# hector_monstertruck_shield.net
KiCad netlist of a schematic drawn in EAGLE
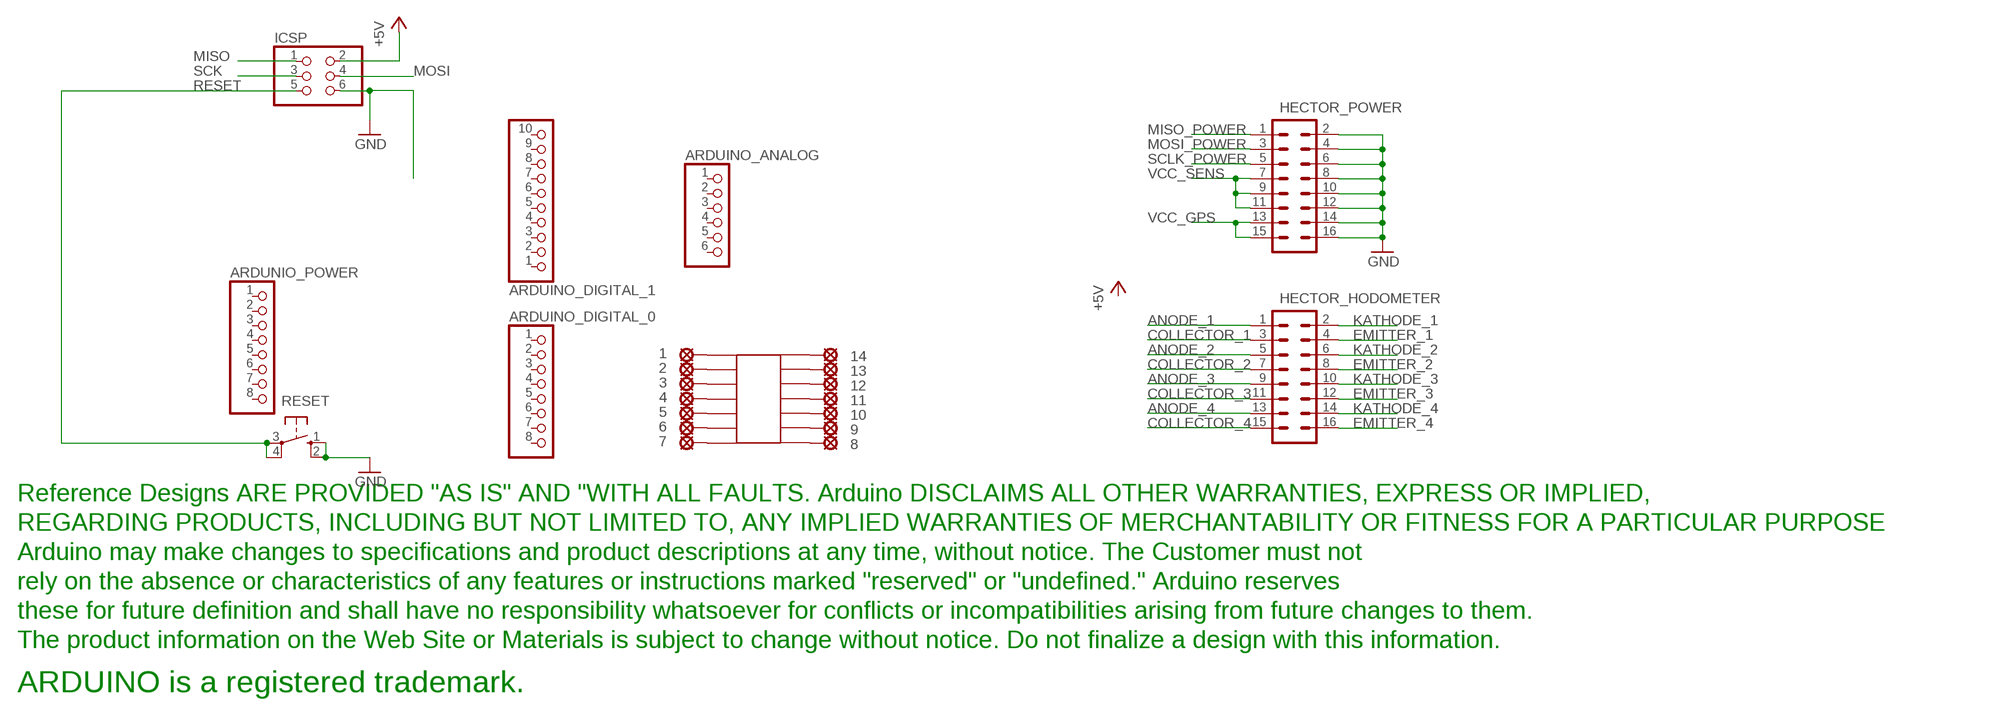
[diagram p0: schematic, sheet 1]
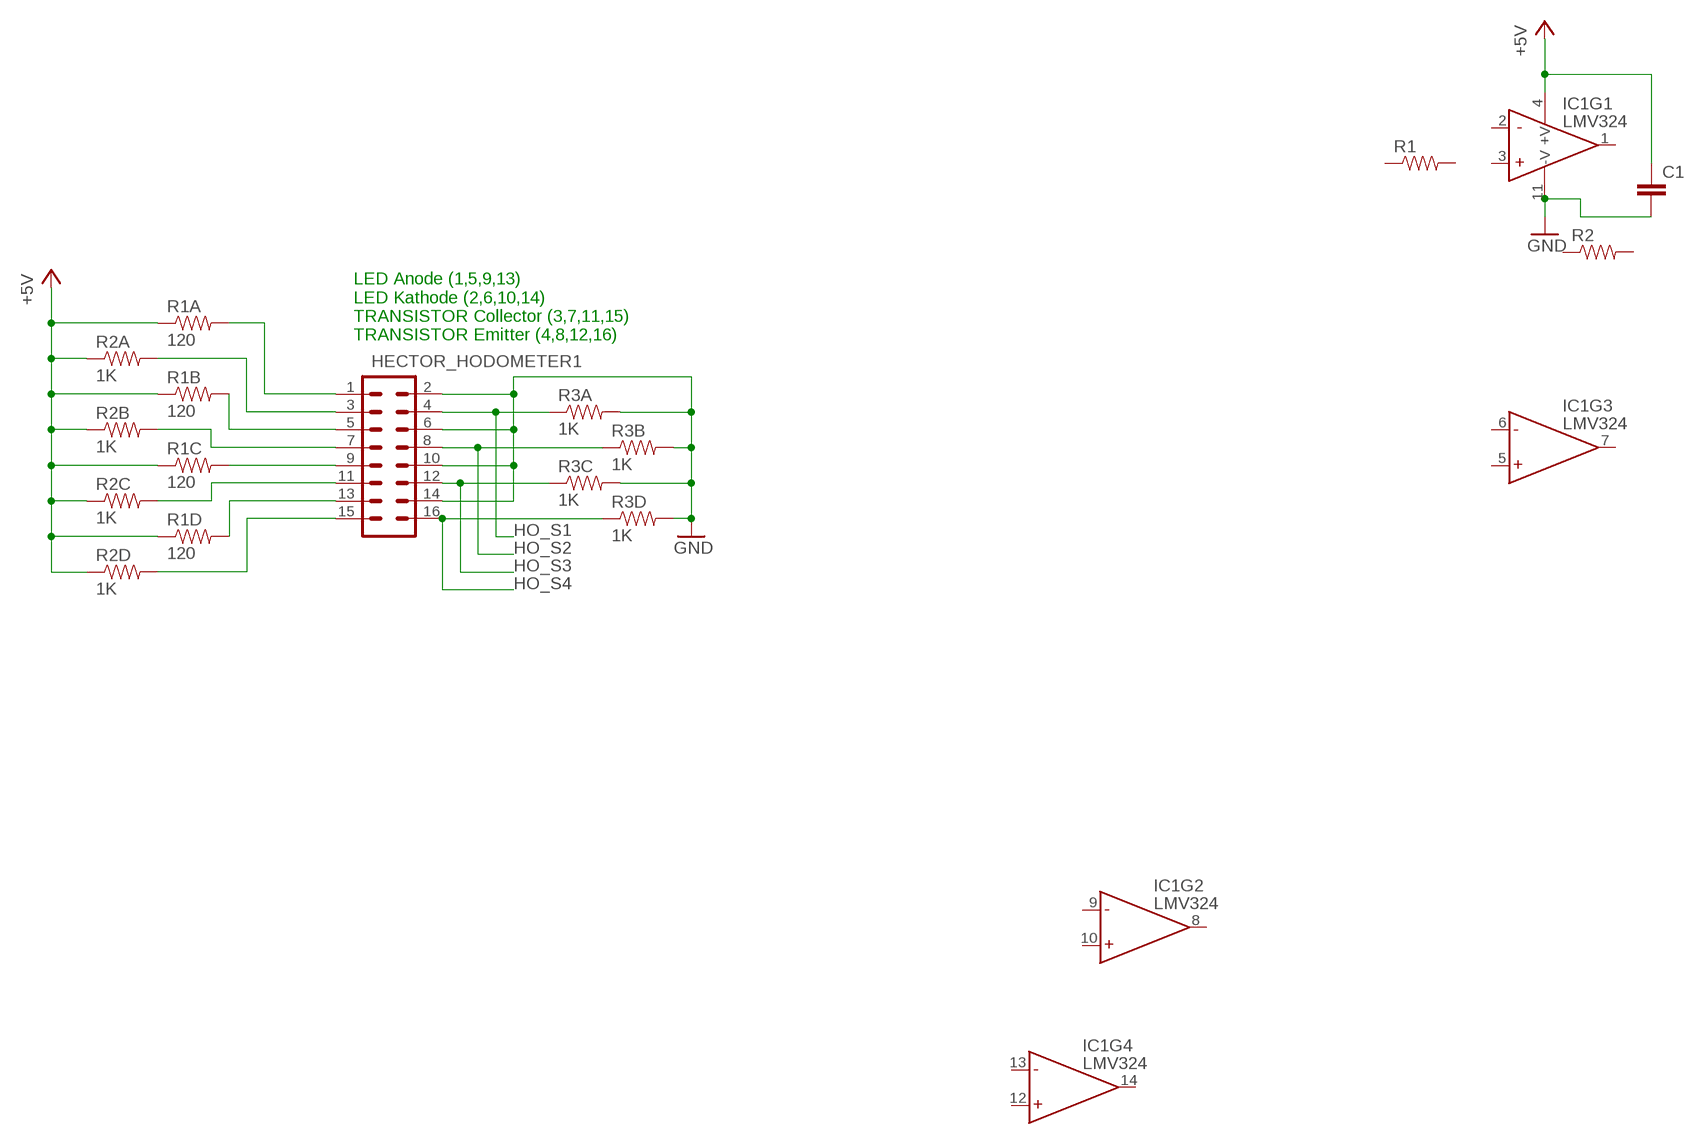
[diagram p1: schematic, sheet 2]

(export (version "E")
  (design (tool "Eeschema 10.0.6"))
  (components
    (comp (ref "C1")
      (value "CAPPTH")
      (footprint "eagle-import:CAP-PTH-SMALL")
      (libsource (lib "eagle-import") (part "CAPPTH"))
    )
    (comp (ref "HECTOR_HODOMETER1")
      (value "M08X2")
      (footprint "eagle-import:2X8")
      (libsource (lib "eagle-import") (part "M08X2"))
    )
    (comp (ref "IC1")
      (value "LMV324")
      (footprint "eagle-import:SO014")
      (libsource (lib "eagle-import") (part "LMV324"))
    )
    (comp (ref "R1")
      (value "RESISTORPTH-1/4W")
      (footprint "eagle-import:AXIAL-0.4")
      (libsource (lib "eagle-import") (part "RESISTORPTH-1/4W"))
    )
    (comp (ref "R1A")
      (value "120")
      (footprint "eagle-import:AXIAL-0.4")
      (libsource (lib "eagle-import") (part "RESISTORPTH-1/4W"))
    )
    (comp (ref "R1B")
      (value "120")
      (footprint "eagle-import:AXIAL-0.4")
      (libsource (lib "eagle-import") (part "RESISTORPTH-1/4W"))
    )
    (comp (ref "R1C")
      (value "120")
      (footprint "eagle-import:AXIAL-0.4")
      (libsource (lib "eagle-import") (part "RESISTORPTH-1/4W"))
    )
    (comp (ref "R1D")
      (value "120")
      (footprint "eagle-import:AXIAL-0.4")
      (libsource (lib "eagle-import") (part "RESISTORPTH-1/4W"))
    )
    (comp (ref "R2")
      (value "RESISTORPTH-1/4W")
      (footprint "eagle-import:AXIAL-0.4")
      (libsource (lib "eagle-import") (part "RESISTORPTH-1/4W"))
    )
    (comp (ref "R2A")
      (value "1K")
      (footprint "eagle-import:AXIAL-0.4")
      (libsource (lib "eagle-import") (part "RESISTORPTH-1/4W"))
    )
    (comp (ref "R2B")
      (value "1K")
      (footprint "eagle-import:AXIAL-0.4")
      (libsource (lib "eagle-import") (part "RESISTORPTH-1/4W"))
    )
    (comp (ref "R2C")
      (value "1K")
      (footprint "eagle-import:AXIAL-0.4")
      (libsource (lib "eagle-import") (part "RESISTORPTH-1/4W"))
    )
    (comp (ref "R2D")
      (value "1K")
      (footprint "eagle-import:AXIAL-0.4")
      (libsource (lib "eagle-import") (part "RESISTORPTH-1/4W"))
    )
    (comp (ref "R3A")
      (value "1K")
      (footprint "eagle-import:AXIAL-0.4")
      (libsource (lib "eagle-import") (part "RESISTORPTH-1/4W"))
    )
    (comp (ref "R3B")
      (value "1K")
      (footprint "eagle-import:AXIAL-0.4")
      (libsource (lib "eagle-import") (part "RESISTORPTH-1/4W"))
    )
    (comp (ref "R3C")
      (value "1K")
      (footprint "eagle-import:AXIAL-0.4")
      (libsource (lib "eagle-import") (part "RESISTORPTH-1/4W"))
    )
    (comp (ref "R3D")
      (value "1K")
      (footprint "eagle-import:AXIAL-0.4")
      (libsource (lib "eagle-import") (part "RESISTORPTH-1/4W"))
    )
    (comp (ref "1")
      (value "LSP10")
      (footprint "eagle-import:LSP10")
      (libsource (lib "eagle-import") (part "LSP10"))
    )
    (comp (ref "2")
      (value "LSP10")
      (footprint "eagle-import:LSP10")
      (libsource (lib "eagle-import") (part "LSP10"))
    )
    (comp (ref "3")
      (value "LSP10")
      (footprint "eagle-import:LSP10")
      (libsource (lib "eagle-import") (part "LSP10"))
    )
    (comp (ref "4")
      (value "LSP10")
      (footprint "eagle-import:LSP10")
      (libsource (lib "eagle-import") (part "LSP10"))
    )
    (comp (ref "5")
      (value "LSP10")
      (footprint "eagle-import:LSP10")
      (libsource (lib "eagle-import") (part "LSP10"))
    )
    (comp (ref "6")
      (value "LSP10")
      (footprint "eagle-import:LSP10")
      (libsource (lib "eagle-import") (part "LSP10"))
    )
    (comp (ref "7")
      (value "LSP10")
      (footprint "eagle-import:LSP10")
      (libsource (lib "eagle-import") (part "LSP10"))
    )
    (comp (ref "8")
      (value "LSP10")
      (footprint "eagle-import:LSP10")
      (libsource (lib "eagle-import") (part "LSP10"))
    )
    (comp (ref "9")
      (value "LSP10")
      (footprint "eagle-import:LSP10")
      (libsource (lib "eagle-import") (part "LSP10"))
    )
    (comp (ref "10")
      (value "LSP10")
      (footprint "eagle-import:LSP10")
      (libsource (lib "eagle-import") (part "LSP10"))
    )
    (comp (ref "11")
      (value "LSP10")
      (footprint "eagle-import:LSP10")
      (libsource (lib "eagle-import") (part "LSP10"))
    )
    (comp (ref "12")
      (value "LSP10")
      (footprint "eagle-import:LSP10")
      (libsource (lib "eagle-import") (part "LSP10"))
    )
    (comp (ref "13")
      (value "LSP10")
      (footprint "eagle-import:LSP10")
      (libsource (lib "eagle-import") (part "LSP10"))
    )
    (comp (ref "14")
      (value "LSP10")
      (footprint "eagle-import:LSP10")
      (libsource (lib "eagle-import") (part "LSP10"))
    )
    (comp (ref "ARDUINO_ANALOG")
      (value "PINHD-1X6")
      (footprint "eagle-import:1X06")
      (libsource (lib "eagle-import") (part "PINHD-1X6"))
    )
    (comp (ref "ARDUINO_DIGITAL_0")
      (value "PINHD-1X8TH")
      (footprint "eagle-import:1X08-TH")
      (libsource (lib "eagle-import") (part "PINHD-1X8TH"))
    )
    (comp (ref "ARDUINO_DIGITAL_1")
      (value "PINHD-1X10TH")
      (footprint "eagle-import:1X10-TH")
      (libsource (lib "eagle-import") (part "PINHD-1X10TH"))
    )
    (comp (ref "ARDUNIO_POWER")
      (value "PINHD-1X8TH")
      (footprint "eagle-import:1X08-TH")
      (libsource (lib "eagle-import") (part "PINHD-1X8TH"))
    )
    (comp (ref "HECTOR_HODOMETER")
      (value "M08X2")
      (footprint "eagle-import:2X8")
      (libsource (lib "eagle-import") (part "M08X2"))
    )
    (comp (ref "HECTOR_POWER")
      (value "M08X2")
      (footprint "eagle-import:2X8")
      (libsource (lib "eagle-import") (part "M08X2"))
    )
    (comp (ref "IC2")
      (value "SMD-14")
      (footprint "eagle-import:SO-14NMW")
      (libsource (lib "eagle-import") (part "SMD-14"))
    )
    (comp (ref "ICSP")
      (value "PINHD-2X3")
      (footprint "eagle-import:2X03")
      (libsource (lib "eagle-import") (part "PINHD-2X3"))
    )
    (comp (ref "RESET")
      (value "10-XX")
      (footprint "eagle-import:B3F-10XX")
      (libsource (lib "eagle-import") (part "10-XX"))
    )
    (comp (ref "U$1")
      (value "DISCLAIMER")
      (footprint "eagle-import:DISCLAIMER")
      (libsource (lib "eagle-import") (part "DISCLAIMER"))
    )
  )
  (nets
    (net (code "1") (name "+5V") (class "Default")
      (node (ref "C1") (pin "1") (pinfunction "1_1") (pintype "passive"))
      (node (ref "IC1") (pin "4") (pinfunction "+V_4") (pintype "power_in"))
      (node (ref "ICSP") (pin "2") (pinfunction "2_2") (pintype "passive"))
      (node (ref "R1A") (pin "P$1") (pinfunction "1_P$1") (pintype "passive"))
      (node (ref "R1B") (pin "P$1") (pinfunction "1_P$1") (pintype "passive"))
      (node (ref "R1C") (pin "P$1") (pinfunction "1_P$1") (pintype "passive"))
      (node (ref "R1D") (pin "P$1") (pinfunction "1_P$1") (pintype "passive"))
      (node (ref "R2A") (pin "P$1") (pinfunction "1_P$1") (pintype "passive"))
      (node (ref "R2B") (pin "P$1") (pinfunction "1_P$1") (pintype "passive"))
      (node (ref "R2C") (pin "P$1") (pinfunction "1_P$1") (pintype "passive"))
      (node (ref "R2D") (pin "P$1") (pinfunction "1_P$1") (pintype "passive"))
    )
    (net (code "2") (name "ANODE_1") (class "Default")
      (node (ref "HECTOR_HODOMETER") (pin "1") (pinfunction "1_1") (pintype "passive"))
    )
    (net (code "3") (name "ANODE_2") (class "Default")
      (node (ref "HECTOR_HODOMETER") (pin "5") (pinfunction "5_5") (pintype "passive"))
    )
    (net (code "4") (name "ANODE_3") (class "Default")
      (node (ref "HECTOR_HODOMETER") (pin "9") (pinfunction "9_9") (pintype "passive"))
    )
    (net (code "5") (name "ANODE_4") (class "Default")
      (node (ref "HECTOR_HODOMETER") (pin "13") (pinfunction "13_13") (pintype "passive"))
    )
    (net (code "6") (name "COLLECTOR_1") (class "Default")
      (node (ref "HECTOR_HODOMETER") (pin "3") (pinfunction "3_3") (pintype "passive"))
    )
    (net (code "7") (name "COLLECTOR_2") (class "Default")
      (node (ref "HECTOR_HODOMETER") (pin "7") (pinfunction "7_7") (pintype "passive"))
    )
    (net (code "8") (name "COLLECTOR_3") (class "Default")
      (node (ref "HECTOR_HODOMETER") (pin "11") (pinfunction "11_11") (pintype "passive"))
    )
    (net (code "9") (name "COLLECTOR_4") (class "Default")
      (node (ref "HECTOR_HODOMETER") (pin "15") (pinfunction "15_15") (pintype "passive"))
    )
    (net (code "10") (name "EMITTER_1") (class "Default")
      (node (ref "HECTOR_HODOMETER") (pin "4") (pinfunction "4_4") (pintype "passive"))
    )
    (net (code "11") (name "EMITTER_2") (class "Default")
      (node (ref "HECTOR_HODOMETER") (pin "8") (pinfunction "8_8") (pintype "passive"))
    )
    (net (code "12") (name "EMITTER_3") (class "Default")
      (node (ref "HECTOR_HODOMETER") (pin "12") (pinfunction "12_12") (pintype "passive"))
    )
    (net (code "13") (name "EMITTER_4") (class "Default")
      (node (ref "HECTOR_HODOMETER") (pin "16") (pinfunction "16_16") (pintype "passive"))
    )
    (net (code "14") (name "GND") (class "Default")
      (node (ref "C1") (pin "2") (pinfunction "2_2") (pintype "passive"))
      (node (ref "HECTOR_HODOMETER1") (pin "10") (pinfunction "10_10") (pintype "passive"))
      (node (ref "HECTOR_HODOMETER1") (pin "14") (pinfunction "14_14") (pintype "passive"))
      (node (ref "HECTOR_HODOMETER1") (pin "2") (pinfunction "2_2") (pintype "passive"))
      (node (ref "HECTOR_HODOMETER1") (pin "6") (pinfunction "6_6") (pintype "passive"))
      (node (ref "HECTOR_POWER") (pin "10") (pinfunction "10_10") (pintype "passive"))
      (node (ref "HECTOR_POWER") (pin "12") (pinfunction "12_12") (pintype "passive"))
      (node (ref "HECTOR_POWER") (pin "14") (pinfunction "14_14") (pintype "passive"))
      (node (ref "HECTOR_POWER") (pin "16") (pinfunction "16_16") (pintype "passive"))
      (node (ref "HECTOR_POWER") (pin "2") (pinfunction "2_2") (pintype "passive"))
      (node (ref "HECTOR_POWER") (pin "4") (pinfunction "4_4") (pintype "passive"))
      (node (ref "HECTOR_POWER") (pin "6") (pinfunction "6_6") (pintype "passive"))
      (node (ref "HECTOR_POWER") (pin "8") (pinfunction "8_8") (pintype "passive"))
      (node (ref "IC1") (pin "11") (pinfunction "-V_11") (pintype "power_in"))
      (node (ref "ICSP") (pin "6") (pinfunction "6_6") (pintype "passive"))
      (node (ref "R3A") (pin "P$2") (pinfunction "2_P$2") (pintype "passive"))
      (node (ref "R3B") (pin "P$2") (pinfunction "2_P$2") (pintype "passive"))
      (node (ref "R3C") (pin "P$2") (pinfunction "2_P$2") (pintype "passive"))
      (node (ref "R3D") (pin "P$2") (pinfunction "2_P$2") (pintype "passive"))
      (node (ref "RESET") (pin "1") (pinfunction "S_1") (pintype "passive"))
      (node (ref "RESET") (pin "2") (pinfunction "S1_2") (pintype "passive"))
    )
    (net (code "15") (name "HO_S1") (class "Default")
      (node (ref "HECTOR_HODOMETER1") (pin "4") (pinfunction "4_4") (pintype "passive"))
      (node (ref "R3A") (pin "P$1") (pinfunction "1_P$1") (pintype "passive"))
    )
    (net (code "16") (name "HO_S2") (class "Default")
      (node (ref "HECTOR_HODOMETER1") (pin "8") (pinfunction "8_8") (pintype "passive"))
      (node (ref "R3B") (pin "P$1") (pinfunction "1_P$1") (pintype "passive"))
    )
    (net (code "17") (name "HO_S3") (class "Default")
      (node (ref "HECTOR_HODOMETER1") (pin "12") (pinfunction "12_12") (pintype "passive"))
      (node (ref "R3C") (pin "P$1") (pinfunction "1_P$1") (pintype "passive"))
    )
    (net (code "18") (name "HO_S4") (class "Default")
      (node (ref "HECTOR_HODOMETER1") (pin "16") (pinfunction "16_16") (pintype "passive"))
      (node (ref "R3D") (pin "P$1") (pinfunction "1_P$1") (pintype "passive"))
    )
    (net (code "19") (name "KATHODE_1") (class "Default")
      (node (ref "HECTOR_HODOMETER") (pin "2") (pinfunction "2_2") (pintype "passive"))
    )
    (net (code "20") (name "KATHODE_2") (class "Default")
      (node (ref "HECTOR_HODOMETER") (pin "6") (pinfunction "6_6") (pintype "passive"))
    )
    (net (code "21") (name "KATHODE_3") (class "Default")
      (node (ref "HECTOR_HODOMETER") (pin "10") (pinfunction "10_10") (pintype "passive"))
    )
    (net (code "22") (name "KATHODE_4") (class "Default")
      (node (ref "HECTOR_HODOMETER") (pin "14") (pinfunction "14_14") (pintype "passive"))
    )
    (net (code "23") (name "MISO") (class "Default")
      (node (ref "ICSP") (pin "1") (pinfunction "1_1") (pintype "passive"))
    )
    (net (code "24") (name "MISO_POWER") (class "Default")
      (node (ref "HECTOR_POWER") (pin "1") (pinfunction "1_1") (pintype "passive"))
    )
    (net (code "25") (name "MOSI") (class "Default")
      (node (ref "ICSP") (pin "4") (pinfunction "4_4") (pintype "passive"))
    )
    (net (code "26") (name "MOSI_POWER") (class "Default")
      (node (ref "HECTOR_POWER") (pin "3") (pinfunction "3_3") (pintype "passive"))
    )
    (net (code "27") (name "Net-(1-PadMP)") (class "Default")
      (node (ref "1") (pin "MP") (pinfunction "MP_MP") (pintype "passive"))
      (node (ref "IC2") (pin "P$1") (pinfunction "P$1_P$1") (pintype "bidirectional"))
    )
    (net (code "28") (name "Net-(2-PadMP)") (class "Default")
      (node (ref "2") (pin "MP") (pinfunction "MP_MP") (pintype "passive"))
      (node (ref "IC2") (pin "P$2") (pinfunction "P$2_P$2") (pintype "bidirectional"))
    )
    (net (code "29") (name "Net-(3-PadMP)") (class "Default")
      (node (ref "3") (pin "MP") (pinfunction "MP_MP") (pintype "passive"))
      (node (ref "IC2") (pin "P$3") (pinfunction "P$3_P$3") (pintype "bidirectional"))
    )
    (net (code "30") (name "Net-(4-PadMP)") (class "Default")
      (node (ref "4") (pin "MP") (pinfunction "MP_MP") (pintype "passive"))
      (node (ref "IC2") (pin "P$4") (pinfunction "P$4_P$4") (pintype "bidirectional"))
    )
    (net (code "31") (name "Net-(5-PadMP)") (class "Default")
      (node (ref "5") (pin "MP") (pinfunction "MP_MP") (pintype "passive"))
      (node (ref "IC2") (pin "P$5") (pinfunction "P$5_P$5") (pintype "bidirectional"))
    )
    (net (code "32") (name "Net-(6-PadMP)") (class "Default")
      (node (ref "6") (pin "MP") (pinfunction "MP_MP") (pintype "passive"))
      (node (ref "IC2") (pin "P$6") (pinfunction "P$6_P$6") (pintype "bidirectional"))
    )
    (net (code "33") (name "Net-(7-PadMP)") (class "Default")
      (node (ref "7") (pin "MP") (pinfunction "MP_MP") (pintype "passive"))
      (node (ref "IC2") (pin "P$7") (pinfunction "P$7_P$7") (pintype "bidirectional"))
    )
    (net (code "34") (name "Net-(8-PadMP)") (class "Default")
      (node (ref "8") (pin "MP") (pinfunction "MP_MP") (pintype "passive"))
      (node (ref "IC2") (pin "P$8") (pinfunction "P$8_P$8") (pintype "bidirectional"))
    )
    (net (code "35") (name "Net-(9-PadMP)") (class "Default")
      (node (ref "9") (pin "MP") (pinfunction "MP_MP") (pintype "passive"))
      (node (ref "IC2") (pin "P$9") (pinfunction "P$9_P$9") (pintype "bidirectional"))
    )
    (net (code "36") (name "Net-(10-PadMP)") (class "Default")
      (node (ref "10") (pin "MP") (pinfunction "MP_MP") (pintype "passive"))
      (node (ref "IC2") (pin "P$10") (pinfunction "P$10_P$10") (pintype "bidirectional"))
    )
    (net (code "37") (name "Net-(11-PadMP)") (class "Default")
      (node (ref "11") (pin "MP") (pinfunction "MP_MP") (pintype "passive"))
      (node (ref "IC2") (pin "P$11") (pinfunction "P$11_P$11") (pintype "bidirectional"))
    )
    (net (code "38") (name "Net-(12-PadMP)") (class "Default")
      (node (ref "12") (pin "MP") (pinfunction "MP_MP") (pintype "passive"))
      (node (ref "IC2") (pin "P$12") (pinfunction "P$12_P$12") (pintype "bidirectional"))
    )
    (net (code "39") (name "Net-(13-PadMP)") (class "Default")
      (node (ref "13") (pin "MP") (pinfunction "MP_MP") (pintype "passive"))
      (node (ref "IC2") (pin "P$13") (pinfunction "P$13_P$13") (pintype "bidirectional"))
    )
    (net (code "40") (name "Net-(14-PadMP)") (class "Default")
      (node (ref "14") (pin "MP") (pinfunction "MP_MP") (pintype "passive"))
      (node (ref "IC2") (pin "P$14") (pinfunction "P$14_P$14") (pintype "bidirectional"))
    )
    (net (code "41") (name "Net-(R1A-2)") (class "Default")
      (node (ref "HECTOR_HODOMETER1") (pin "1") (pinfunction "1_1") (pintype "passive"))
      (node (ref "R1A") (pin "P$2") (pinfunction "2_P$2") (pintype "passive"))
    )
    (net (code "42") (name "Net-(R1B-2)") (class "Default")
      (node (ref "HECTOR_HODOMETER1") (pin "5") (pinfunction "5_5") (pintype "passive"))
      (node (ref "R1B") (pin "P$2") (pinfunction "2_P$2") (pintype "passive"))
    )
    (net (code "43") (name "Net-(R1C-2)") (class "Default")
      (node (ref "HECTOR_HODOMETER1") (pin "9") (pinfunction "9_9") (pintype "passive"))
      (node (ref "R1C") (pin "P$2") (pinfunction "2_P$2") (pintype "passive"))
    )
    (net (code "44") (name "Net-(R1D-2)") (class "Default")
      (node (ref "HECTOR_HODOMETER1") (pin "13") (pinfunction "13_13") (pintype "passive"))
      (node (ref "R1D") (pin "P$2") (pinfunction "2_P$2") (pintype "passive"))
    )
    (net (code "45") (name "Net-(R2A-2)") (class "Default")
      (node (ref "HECTOR_HODOMETER1") (pin "3") (pinfunction "3_3") (pintype "passive"))
      (node (ref "R2A") (pin "P$2") (pinfunction "2_P$2") (pintype "passive"))
    )
    (net (code "46") (name "Net-(R2B-2)") (class "Default")
      (node (ref "HECTOR_HODOMETER1") (pin "7") (pinfunction "7_7") (pintype "passive"))
      (node (ref "R2B") (pin "P$2") (pinfunction "2_P$2") (pintype "passive"))
    )
    (net (code "47") (name "Net-(R2C-2)") (class "Default")
      (node (ref "HECTOR_HODOMETER1") (pin "11") (pinfunction "11_11") (pintype "passive"))
      (node (ref "R2C") (pin "P$2") (pinfunction "2_P$2") (pintype "passive"))
    )
    (net (code "48") (name "Net-(R2D-2)") (class "Default")
      (node (ref "HECTOR_HODOMETER1") (pin "15") (pinfunction "15_15") (pintype "passive"))
      (node (ref "R2D") (pin "P$2") (pinfunction "2_P$2") (pintype "passive"))
    )
    (net (code "49") (name "RESET") (class "Default")
      (node (ref "ICSP") (pin "5") (pinfunction "5_5") (pintype "passive"))
      (node (ref "RESET") (pin "3") (pinfunction "P_3") (pintype "passive"))
      (node (ref "RESET") (pin "4") (pinfunction "P1_4") (pintype "passive"))
    )
    (net (code "50") (name "SCK") (class "Default")
      (node (ref "ICSP") (pin "3") (pinfunction "3_3") (pintype "passive"))
    )
    (net (code "51") (name "SCLK_POWER") (class "Default")
      (node (ref "HECTOR_POWER") (pin "5") (pinfunction "5_5") (pintype "passive"))
    )
    (net (code "52") (name "VCC_GPS") (class "Default")
      (node (ref "HECTOR_POWER") (pin "13") (pinfunction "13_13") (pintype "passive"))
      (node (ref "HECTOR_POWER") (pin "15") (pinfunction "15_15") (pintype "passive"))
    )
    (net (code "53") (name "VCC_SENS") (class "Default")
      (node (ref "HECTOR_POWER") (pin "11") (pinfunction "11_11") (pintype "passive"))
      (node (ref "HECTOR_POWER") (pin "7") (pinfunction "7_7") (pintype "passive"))
      (node (ref "HECTOR_POWER") (pin "9") (pinfunction "9_9") (pintype "passive"))
    )
    (net (code "54") (name "unconnected-(ARDUINO_ANALOG-Pad1)") (class "Default")
      (node (ref "ARDUINO_ANALOG") (pin "1") (pinfunction "1_1") (pintype "passive"))
    )
    (net (code "55") (name "unconnected-(ARDUINO_ANALOG-Pad2)") (class "Default")
      (node (ref "ARDUINO_ANALOG") (pin "2") (pinfunction "2_2") (pintype "passive"))
    )
    (net (code "56") (name "unconnected-(ARDUINO_ANALOG-Pad3)") (class "Default")
      (node (ref "ARDUINO_ANALOG") (pin "3") (pinfunction "3_3") (pintype "passive"))
    )
    (net (code "57") (name "unconnected-(ARDUINO_ANALOG-Pad4)") (class "Default")
      (node (ref "ARDUINO_ANALOG") (pin "4") (pinfunction "4_4") (pintype "passive"))
    )
    (net (code "58") (name "unconnected-(ARDUINO_ANALOG-Pad5)") (class "Default")
      (node (ref "ARDUINO_ANALOG") (pin "5") (pinfunction "5_5") (pintype "passive"))
    )
    (net (code "59") (name "unconnected-(ARDUINO_ANALOG-Pad6)") (class "Default")
      (node (ref "ARDUINO_ANALOG") (pin "6") (pinfunction "6_6") (pintype "passive"))
    )
    (net (code "60") (name "unconnected-(ARDUINO_DIGITAL_0-Pad1)") (class "Default")
      (node (ref "ARDUINO_DIGITAL_0") (pin "1") (pinfunction "1_1") (pintype "passive"))
    )
    (net (code "61") (name "unconnected-(ARDUINO_DIGITAL_0-Pad2)") (class "Default")
      (node (ref "ARDUINO_DIGITAL_0") (pin "2") (pinfunction "2_2") (pintype "passive"))
    )
    (net (code "62") (name "unconnected-(ARDUINO_DIGITAL_0-Pad3)") (class "Default")
      (node (ref "ARDUINO_DIGITAL_0") (pin "3") (pinfunction "3_3") (pintype "passive"))
    )
    (net (code "63") (name "unconnected-(ARDUINO_DIGITAL_0-Pad4)") (class "Default")
      (node (ref "ARDUINO_DIGITAL_0") (pin "4") (pinfunction "4_4") (pintype "passive"))
    )
    (net (code "64") (name "unconnected-(ARDUINO_DIGITAL_0-Pad5)") (class "Default")
      (node (ref "ARDUINO_DIGITAL_0") (pin "5") (pinfunction "5_5") (pintype "passive"))
    )
    (net (code "65") (name "unconnected-(ARDUINO_DIGITAL_0-Pad6)") (class "Default")
      (node (ref "ARDUINO_DIGITAL_0") (pin "6") (pinfunction "6_6") (pintype "passive"))
    )
    (net (code "66") (name "unconnected-(ARDUINO_DIGITAL_0-Pad7)") (class "Default")
      (node (ref "ARDUINO_DIGITAL_0") (pin "7") (pinfunction "7_7") (pintype "passive"))
    )
    (net (code "67") (name "unconnected-(ARDUINO_DIGITAL_0-Pad8)") (class "Default")
      (node (ref "ARDUINO_DIGITAL_0") (pin "8") (pinfunction "8_8") (pintype "passive"))
    )
    (net (code "68") (name "unconnected-(ARDUINO_DIGITAL_1-Pad1)") (class "Default")
      (node (ref "ARDUINO_DIGITAL_1") (pin "1") (pinfunction "1_1") (pintype "passive"))
    )
    (net (code "69") (name "unconnected-(ARDUINO_DIGITAL_1-Pad2)") (class "Default")
      (node (ref "ARDUINO_DIGITAL_1") (pin "2") (pinfunction "2_2") (pintype "passive"))
    )
    (net (code "70") (name "unconnected-(ARDUINO_DIGITAL_1-Pad3)") (class "Default")
      (node (ref "ARDUINO_DIGITAL_1") (pin "3") (pinfunction "3_3") (pintype "passive"))
    )
    (net (code "71") (name "unconnected-(ARDUINO_DIGITAL_1-Pad4)") (class "Default")
      (node (ref "ARDUINO_DIGITAL_1") (pin "4") (pinfunction "4_4") (pintype "passive"))
    )
    (net (code "72") (name "unconnected-(ARDUINO_DIGITAL_1-Pad5)") (class "Default")
      (node (ref "ARDUINO_DIGITAL_1") (pin "5") (pinfunction "5_5") (pintype "passive"))
    )
    (net (code "73") (name "unconnected-(ARDUINO_DIGITAL_1-Pad6)") (class "Default")
      (node (ref "ARDUINO_DIGITAL_1") (pin "6") (pinfunction "6_6") (pintype "passive"))
    )
    (net (code "74") (name "unconnected-(ARDUINO_DIGITAL_1-Pad7)") (class "Default")
      (node (ref "ARDUINO_DIGITAL_1") (pin "7") (pinfunction "7_7") (pintype "passive"))
    )
    (net (code "75") (name "unconnected-(ARDUINO_DIGITAL_1-Pad8)") (class "Default")
      (node (ref "ARDUINO_DIGITAL_1") (pin "8") (pinfunction "8_8") (pintype "passive"))
    )
    (net (code "76") (name "unconnected-(ARDUINO_DIGITAL_1-Pad9)") (class "Default")
      (node (ref "ARDUINO_DIGITAL_1") (pin "9") (pinfunction "9_9") (pintype "passive"))
    )
    (net (code "77") (name "unconnected-(ARDUINO_DIGITAL_1-Pad10)") (class "Default")
      (node (ref "ARDUINO_DIGITAL_1") (pin "10") (pinfunction "10_10") (pintype "passive"))
    )
    (net (code "78") (name "unconnected-(ARDUNIO_POWER-Pad1)") (class "Default")
      (node (ref "ARDUNIO_POWER") (pin "1") (pinfunction "1_1") (pintype "passive"))
    )
    (net (code "79") (name "unconnected-(ARDUNIO_POWER-Pad2)") (class "Default")
      (node (ref "ARDUNIO_POWER") (pin "2") (pinfunction "2_2") (pintype "passive"))
    )
    (net (code "80") (name "unconnected-(ARDUNIO_POWER-Pad3)") (class "Default")
      (node (ref "ARDUNIO_POWER") (pin "3") (pinfunction "3_3") (pintype "passive"))
    )
    (net (code "81") (name "unconnected-(ARDUNIO_POWER-Pad4)") (class "Default")
      (node (ref "ARDUNIO_POWER") (pin "4") (pinfunction "4_4") (pintype "passive"))
    )
    (net (code "82") (name "unconnected-(ARDUNIO_POWER-Pad5)") (class "Default")
      (node (ref "ARDUNIO_POWER") (pin "5") (pinfunction "5_5") (pintype "passive"))
    )
    (net (code "83") (name "unconnected-(ARDUNIO_POWER-Pad6)") (class "Default")
      (node (ref "ARDUNIO_POWER") (pin "6") (pinfunction "6_6") (pintype "passive"))
    )
    (net (code "84") (name "unconnected-(ARDUNIO_POWER-Pad7)") (class "Default")
      (node (ref "ARDUNIO_POWER") (pin "7") (pinfunction "7_7") (pintype "passive"))
    )
    (net (code "85") (name "unconnected-(ARDUNIO_POWER-Pad8)") (class "Default")
      (node (ref "ARDUNIO_POWER") (pin "8") (pinfunction "8_8") (pintype "passive"))
    )
    (net (code "86") (name "unconnected-(IC1A-+IN-Pad3)") (class "Default")
      (node (ref "IC1") (pin "3") (pinfunction "+IN_3") (pintype "input"))
    )
    (net (code "87") (name "unconnected-(IC1A--IN-Pad2)") (class "Default")
      (node (ref "IC1") (pin "2") (pinfunction "-IN_2") (pintype "input"))
    )
    (net (code "88") (name "unconnected-(IC1A-OUT-Pad1)") (class "Default")
      (node (ref "IC1") (pin "1") (pinfunction "OUT_1") (pintype "output"))
    )
    (net (code "89") (name "unconnected-(IC1B-+IN-Pad10)") (class "Default")
      (node (ref "IC1") (pin "10") (pinfunction "+IN_10") (pintype "input"))
    )
    (net (code "90") (name "unconnected-(IC1B--IN-Pad9)") (class "Default")
      (node (ref "IC1") (pin "9") (pinfunction "-IN_9") (pintype "input"))
    )
    (net (code "91") (name "unconnected-(IC1B-OUT-Pad8)") (class "Default")
      (node (ref "IC1") (pin "8") (pinfunction "OUT_8") (pintype "output"))
    )
    (net (code "92") (name "unconnected-(IC1C-+IN-Pad5)") (class "Default")
      (node (ref "IC1") (pin "5") (pinfunction "+IN_5") (pintype "input"))
    )
    (net (code "93") (name "unconnected-(IC1C--IN-Pad6)") (class "Default")
      (node (ref "IC1") (pin "6") (pinfunction "-IN_6") (pintype "input"))
    )
    (net (code "94") (name "unconnected-(IC1C-OUT-Pad7)") (class "Default")
      (node (ref "IC1") (pin "7") (pinfunction "OUT_7") (pintype "output"))
    )
    (net (code "95") (name "unconnected-(IC1D-+IN-Pad12)") (class "Default")
      (node (ref "IC1") (pin "12") (pinfunction "+IN_12") (pintype "input"))
    )
    (net (code "96") (name "unconnected-(IC1D--IN-Pad13)") (class "Default")
      (node (ref "IC1") (pin "13") (pinfunction "-IN_13") (pintype "input"))
    )
    (net (code "97") (name "unconnected-(IC1D-OUT-Pad14)") (class "Default")
      (node (ref "IC1") (pin "14") (pinfunction "OUT_14") (pintype "output"))
    )
    (net (code "98") (name "unconnected-(R1-1-PadP$1)") (class "Default")
      (node (ref "R1") (pin "P$1") (pinfunction "1_P$1") (pintype "passive"))
    )
    (net (code "99") (name "unconnected-(R1-2-PadP$2)") (class "Default")
      (node (ref "R1") (pin "P$2") (pinfunction "2_P$2") (pintype "passive"))
    )
    (net (code "100") (name "unconnected-(R2-1-PadP$1)") (class "Default")
      (node (ref "R2") (pin "P$1") (pinfunction "1_P$1") (pintype "passive"))
    )
    (net (code "101") (name "unconnected-(R2-2-PadP$2)") (class "Default")
      (node (ref "R2") (pin "P$2") (pinfunction "2_P$2") (pintype "passive"))
    )
  )
)
